# xen_daisy_motherboard.net
KiCad netlist of a schematic drawn in EAGLE
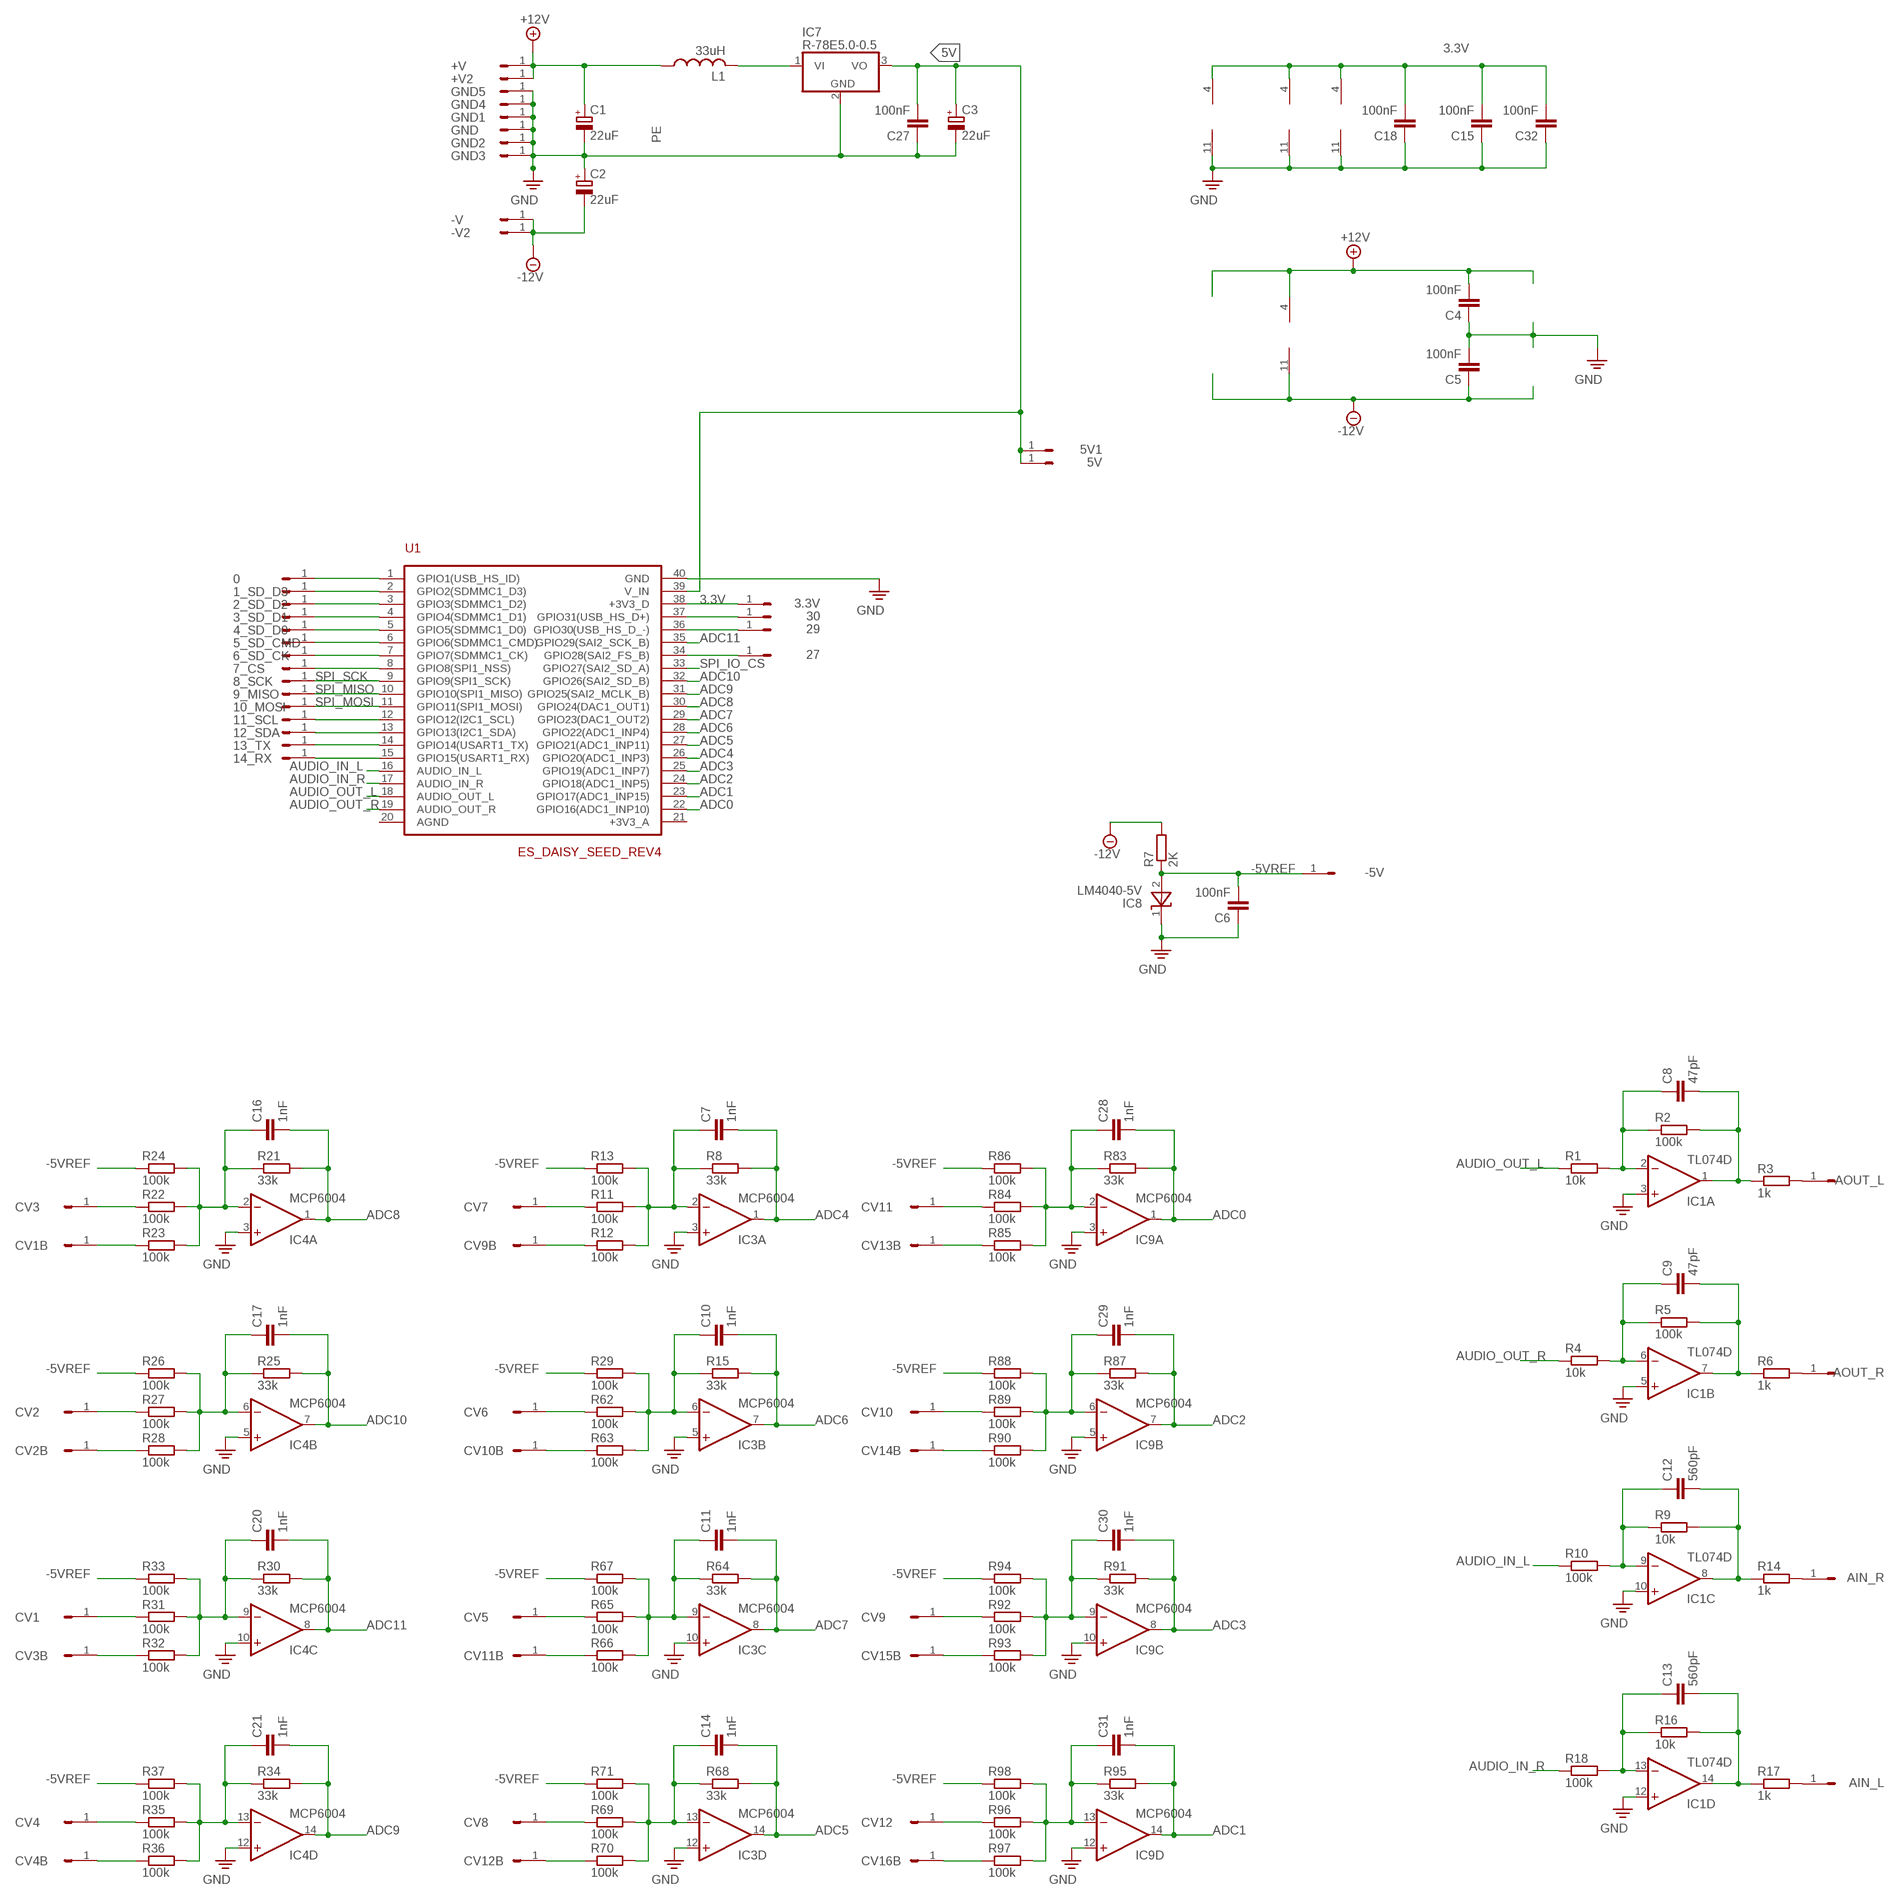
[diagram p0: schematic, sheet 1, part 1 of 2]
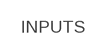
[diagram p1: schematic, sheet 1, part 2 of 2]

(export (version "E")
  (design (tool "Eeschema 10.0.6"))
  (components
    (comp (ref "+V")
      (value "HEADER/MALE/01")
      (footprint "eagle-import:HEADER_MALE_01")
      (fields (field (name "SPICEPREFIX") "X"))
      (libsource (lib "eagle-import") (part "HEADER/MALE/01"))
    )
    (comp (ref "+V2")
      (value "HEADER/MALE/01")
      (footprint "eagle-import:HEADER_MALE_01")
      (fields (field (name "SPICEPREFIX") "X"))
      (libsource (lib "eagle-import") (part "HEADER/MALE/01"))
    )
    (comp (ref "-5V")
      (value "HEADER/MALE/01")
      (footprint "eagle-import:HEADER_MALE_01")
      (fields (field (name "SPICEPREFIX") "X"))
      (libsource (lib "eagle-import") (part "HEADER/MALE/01"))
    )
    (comp (ref "-V")
      (value "HEADER/MALE/01")
      (footprint "eagle-import:HEADER_MALE_01")
      (fields (field (name "SPICEPREFIX") "X"))
      (libsource (lib "eagle-import") (part "HEADER/MALE/01"))
    )
    (comp (ref "-V2")
      (value "HEADER/MALE/01")
      (footprint "eagle-import:HEADER_MALE_01")
      (fields (field (name "SPICEPREFIX") "X"))
      (libsource (lib "eagle-import") (part "HEADER/MALE/01"))
    )
    (comp (ref "0")
      (value "HEADER/MALE/01")
      (footprint "eagle-import:HEADER_MALE_01")
      (fields (field (name "SPICEPREFIX") "X"))
      (libsource (lib "eagle-import") (part "HEADER/MALE/01"))
    )
    (comp (ref "1_SD_D3")
      (value "HEADER/MALE/01")
      (footprint "eagle-import:HEADER_MALE_01")
      (fields (field (name "SPICEPREFIX") "X"))
      (libsource (lib "eagle-import") (part "HEADER/MALE/01"))
    )
    (comp (ref "2_SD_D2")
      (value "HEADER/MALE/01")
      (footprint "eagle-import:HEADER_MALE_01")
      (fields (field (name "SPICEPREFIX") "X"))
      (libsource (lib "eagle-import") (part "HEADER/MALE/01"))
    )
    (comp (ref "3.3V")
      (value "HEADER/MALE/01")
      (footprint "eagle-import:HEADER_MALE_01")
      (fields (field (name "SPICEPREFIX") "X"))
      (libsource (lib "eagle-import") (part "HEADER/MALE/01"))
    )
    (comp (ref "3_SD_D1")
      (value "HEADER/MALE/01")
      (footprint "eagle-import:HEADER_MALE_01")
      (fields (field (name "SPICEPREFIX") "X"))
      (libsource (lib "eagle-import") (part "HEADER/MALE/01"))
    )
    (comp (ref "4_SD_D0")
      (value "HEADER/MALE/01")
      (footprint "eagle-import:HEADER_MALE_01")
      (fields (field (name "SPICEPREFIX") "X"))
      (libsource (lib "eagle-import") (part "HEADER/MALE/01"))
    )
    (comp (ref "5V")
      (value "HEADER/MALE/01")
      (footprint "eagle-import:HEADER_MALE_01")
      (fields (field (name "SPICEPREFIX") "X"))
      (libsource (lib "eagle-import") (part "HEADER/MALE/01"))
    )
    (comp (ref "5V1")
      (value "HEADER/MALE/01")
      (footprint "eagle-import:HEADER_MALE_01")
      (fields (field (name "SPICEPREFIX") "X"))
      (libsource (lib "eagle-import") (part "HEADER/MALE/01"))
    )
    (comp (ref "5_SD_CMD")
      (value "HEADER/MALE/01")
      (footprint "eagle-import:HEADER_MALE_01")
      (fields (field (name "SPICEPREFIX") "X"))
      (libsource (lib "eagle-import") (part "HEADER/MALE/01"))
    )
    (comp (ref "6_SD_CK")
      (value "HEADER/MALE/01")
      (footprint "eagle-import:HEADER_MALE_01")
      (fields (field (name "SPICEPREFIX") "X"))
      (libsource (lib "eagle-import") (part "HEADER/MALE/01"))
    )
    (comp (ref "7_CS")
      (value "HEADER/MALE/01")
      (footprint "eagle-import:HEADER_MALE_01")
      (fields (field (name "SPICEPREFIX") "X"))
      (libsource (lib "eagle-import") (part "HEADER/MALE/01"))
    )
    (comp (ref "8_SCK")
      (value "HEADER/MALE/01")
      (footprint "eagle-import:HEADER_MALE_01")
      (fields (field (name "SPICEPREFIX") "X"))
      (libsource (lib "eagle-import") (part "HEADER/MALE/01"))
    )
    (comp (ref "9_MISO")
      (value "HEADER/MALE/01")
      (footprint "eagle-import:HEADER_MALE_01")
      (fields (field (name "SPICEPREFIX") "X"))
      (libsource (lib "eagle-import") (part "HEADER/MALE/01"))
    )
    (comp (ref "10_MOSI")
      (value "HEADER/MALE/01")
      (footprint "eagle-import:HEADER_MALE_01")
      (fields (field (name "SPICEPREFIX") "X"))
      (libsource (lib "eagle-import") (part "HEADER/MALE/01"))
    )
    (comp (ref "11_SCL")
      (value "HEADER/MALE/01")
      (footprint "eagle-import:HEADER_MALE_01")
      (fields (field (name "SPICEPREFIX") "X"))
      (libsource (lib "eagle-import") (part "HEADER/MALE/01"))
    )
    (comp (ref "12_SDA")
      (value "HEADER/MALE/01")
      (footprint "eagle-import:HEADER_MALE_01")
      (fields (field (name "SPICEPREFIX") "X"))
      (libsource (lib "eagle-import") (part "HEADER/MALE/01"))
    )
    (comp (ref "13_TX")
      (value "HEADER/MALE/01")
      (footprint "eagle-import:HEADER_MALE_01")
      (fields (field (name "SPICEPREFIX") "X"))
      (libsource (lib "eagle-import") (part "HEADER/MALE/01"))
    )
    (comp (ref "14_RX")
      (value "HEADER/MALE/01")
      (footprint "eagle-import:HEADER_MALE_01")
      (fields (field (name "SPICEPREFIX") "X"))
      (libsource (lib "eagle-import") (part "HEADER/MALE/01"))
    )
    (comp (ref "27")
      (value "HEADER/MALE/01")
      (footprint "eagle-import:HEADER_MALE_01")
      (fields (field (name "SPICEPREFIX") "X"))
      (libsource (lib "eagle-import") (part "HEADER/MALE/01"))
    )
    (comp (ref "29")
      (value "HEADER/MALE/01")
      (footprint "eagle-import:HEADER_MALE_01")
      (fields (field (name "SPICEPREFIX") "X"))
      (libsource (lib "eagle-import") (part "HEADER/MALE/01"))
    )
    (comp (ref "30")
      (value "HEADER/MALE/01")
      (footprint "eagle-import:HEADER_MALE_01")
      (fields (field (name "SPICEPREFIX") "X"))
      (libsource (lib "eagle-import") (part "HEADER/MALE/01"))
    )
    (comp (ref "AIN_L")
      (value "HEADER/MALE/01")
      (footprint "eagle-import:HEADER_MALE_01")
      (fields (field (name "SPICEPREFIX") "X"))
      (libsource (lib "eagle-import") (part "HEADER/MALE/01"))
    )
    (comp (ref "AIN_R")
      (value "HEADER/MALE/01")
      (footprint "eagle-import:HEADER_MALE_01")
      (fields (field (name "SPICEPREFIX") "X"))
      (libsource (lib "eagle-import") (part "HEADER/MALE/01"))
    )
    (comp (ref "AOUT_L")
      (value "HEADER/MALE/01")
      (footprint "eagle-import:HEADER_MALE_01")
      (fields (field (name "SPICEPREFIX") "X"))
      (libsource (lib "eagle-import") (part "HEADER/MALE/01"))
    )
    (comp (ref "AOUT_R")
      (value "HEADER/MALE/01")
      (footprint "eagle-import:HEADER_MALE_01")
      (fields (field (name "SPICEPREFIX") "X"))
      (libsource (lib "eagle-import") (part "HEADER/MALE/01"))
    )
    (comp (ref "C1")
      (value "22uF")
      (footprint "eagle-import:PANASONIC_A")
      (fields (field (name "SPICEPREFIX") "C"))
      (libsource (lib "eagle-import") (part "CAPACITOR/POLARIZED"))
    )
    (comp (ref "C2")
      (value "22uF")
      (footprint "eagle-import:PANASONIC_A")
      (fields (field (name "SPICEPREFIX") "C"))
      (libsource (lib "eagle-import") (part "CAPACITOR/POLARIZED"))
    )
    (comp (ref "C3")
      (value "22uF")
      (footprint "eagle-import:PANASONIC_A")
      (fields (field (name "SPICEPREFIX") "C"))
      (libsource (lib "eagle-import") (part "CAPACITOR/POLARIZED"))
    )
    (comp (ref "C4")
      (value "100nF")
      (footprint "eagle-import:C0603")
      (libsource (lib "eagle-import") (part "CAPACITORC0603"))
    )
    (comp (ref "C5")
      (value "100nF")
      (footprint "eagle-import:C0603")
      (libsource (lib "eagle-import") (part "CAPACITORC0603"))
    )
    (comp (ref "C6")
      (value "100nF")
      (footprint "eagle-import:C0603")
      (libsource (lib "eagle-import") (part "CAPACITORC0603"))
    )
    (comp (ref "C7")
      (value "1nF")
      (footprint "eagle-import:C0603")
      (libsource (lib "eagle-import") (part "CAPACITORC0603"))
    )
    (comp (ref "C8")
      (value "47pF")
      (footprint "eagle-import:C0603")
      (libsource (lib "eagle-import") (part "CAPACITORC0603"))
    )
    (comp (ref "C9")
      (value "47pF")
      (footprint "eagle-import:C0603")
      (libsource (lib "eagle-import") (part "CAPACITORC0603"))
    )
    (comp (ref "C10")
      (value "1nF")
      (footprint "eagle-import:C0603")
      (libsource (lib "eagle-import") (part "CAPACITORC0603"))
    )
    (comp (ref "C11")
      (value "1nF")
      (footprint "eagle-import:C0603")
      (libsource (lib "eagle-import") (part "CAPACITORC0603"))
    )
    (comp (ref "C12")
      (value "560pF")
      (footprint "eagle-import:C0603")
      (libsource (lib "eagle-import") (part "CAPACITORC0603"))
    )
    (comp (ref "C13")
      (value "560pF")
      (footprint "eagle-import:C0603")
      (libsource (lib "eagle-import") (part "CAPACITORC0603"))
    )
    (comp (ref "C14")
      (value "1nF")
      (footprint "eagle-import:C0603")
      (libsource (lib "eagle-import") (part "CAPACITORC0603"))
    )
    (comp (ref "C15")
      (value "100nF")
      (footprint "eagle-import:C0603")
      (libsource (lib "eagle-import") (part "CAPACITORC0603"))
    )
    (comp (ref "C16")
      (value "1nF")
      (footprint "eagle-import:C0603")
      (libsource (lib "eagle-import") (part "CAPACITORC0603"))
    )
    (comp (ref "C17")
      (value "1nF")
      (footprint "eagle-import:C0603")
      (libsource (lib "eagle-import") (part "CAPACITORC0603"))
    )
    (comp (ref "C18")
      (value "100nF")
      (footprint "eagle-import:C0603")
      (libsource (lib "eagle-import") (part "CAPACITORC0603"))
    )
    (comp (ref "C20")
      (value "1nF")
      (footprint "eagle-import:C0603")
      (libsource (lib "eagle-import") (part "CAPACITORC0603"))
    )
    (comp (ref "C21")
      (value "1nF")
      (footprint "eagle-import:C0603")
      (libsource (lib "eagle-import") (part "CAPACITORC0603"))
    )
    (comp (ref "C27")
      (value "100nF")
      (footprint "eagle-import:C0603")
      (libsource (lib "eagle-import") (part "CAPACITORC0603"))
    )
    (comp (ref "C28")
      (value "1nF")
      (footprint "eagle-import:C0603")
      (libsource (lib "eagle-import") (part "CAPACITORC0603"))
    )
    (comp (ref "C29")
      (value "1nF")
      (footprint "eagle-import:C0603")
      (libsource (lib "eagle-import") (part "CAPACITORC0603"))
    )
    (comp (ref "C30")
      (value "1nF")
      (footprint "eagle-import:C0603")
      (libsource (lib "eagle-import") (part "CAPACITORC0603"))
    )
    (comp (ref "C31")
      (value "1nF")
      (footprint "eagle-import:C0603")
      (libsource (lib "eagle-import") (part "CAPACITORC0603"))
    )
    (comp (ref "C32")
      (value "100nF")
      (footprint "eagle-import:C0603")
      (libsource (lib "eagle-import") (part "CAPACITORC0603"))
    )
    (comp (ref "CV1")
      (value "HEADER/MALE/01")
      (footprint "eagle-import:HEADER_MALE_01")
      (fields (field (name "SPICEPREFIX") "X"))
      (libsource (lib "eagle-import") (part "HEADER/MALE/01"))
    )
    (comp (ref "CV1B")
      (value "HEADER/MALE/01")
      (footprint "eagle-import:HEADER_MALE_01")
      (fields (field (name "SPICEPREFIX") "X"))
      (libsource (lib "eagle-import") (part "HEADER/MALE/01"))
    )
    (comp (ref "CV2")
      (value "HEADER/MALE/01")
      (footprint "eagle-import:HEADER_MALE_01")
      (fields (field (name "SPICEPREFIX") "X"))
      (libsource (lib "eagle-import") (part "HEADER/MALE/01"))
    )
    (comp (ref "CV2B")
      (value "HEADER/MALE/01")
      (footprint "eagle-import:HEADER_MALE_01")
      (fields (field (name "SPICEPREFIX") "X"))
      (libsource (lib "eagle-import") (part "HEADER/MALE/01"))
    )
    (comp (ref "CV3")
      (value "HEADER/MALE/01")
      (footprint "eagle-import:HEADER_MALE_01")
      (fields (field (name "SPICEPREFIX") "X"))
      (libsource (lib "eagle-import") (part "HEADER/MALE/01"))
    )
    (comp (ref "CV3B")
      (value "HEADER/MALE/01")
      (footprint "eagle-import:HEADER_MALE_01")
      (fields (field (name "SPICEPREFIX") "X"))
      (libsource (lib "eagle-import") (part "HEADER/MALE/01"))
    )
    (comp (ref "CV4")
      (value "HEADER/MALE/01")
      (footprint "eagle-import:HEADER_MALE_01")
      (fields (field (name "SPICEPREFIX") "X"))
      (libsource (lib "eagle-import") (part "HEADER/MALE/01"))
    )
    (comp (ref "CV4B")
      (value "HEADER/MALE/01")
      (footprint "eagle-import:HEADER_MALE_01")
      (fields (field (name "SPICEPREFIX") "X"))
      (libsource (lib "eagle-import") (part "HEADER/MALE/01"))
    )
    (comp (ref "CV5")
      (value "HEADER/MALE/01")
      (footprint "eagle-import:HEADER_MALE_01")
      (fields (field (name "SPICEPREFIX") "X"))
      (libsource (lib "eagle-import") (part "HEADER/MALE/01"))
    )
    (comp (ref "CV6")
      (value "HEADER/MALE/01")
      (footprint "eagle-import:HEADER_MALE_01")
      (fields (field (name "SPICEPREFIX") "X"))
      (libsource (lib "eagle-import") (part "HEADER/MALE/01"))
    )
    (comp (ref "CV7")
      (value "HEADER/MALE/01")
      (footprint "eagle-import:HEADER_MALE_01")
      (fields (field (name "SPICEPREFIX") "X"))
      (libsource (lib "eagle-import") (part "HEADER/MALE/01"))
    )
    (comp (ref "CV8")
      (value "HEADER/MALE/01")
      (footprint "eagle-import:HEADER_MALE_01")
      (fields (field (name "SPICEPREFIX") "X"))
      (libsource (lib "eagle-import") (part "HEADER/MALE/01"))
    )
    (comp (ref "CV9")
      (value "HEADER/MALE/01")
      (footprint "eagle-import:HEADER_MALE_01")
      (fields (field (name "SPICEPREFIX") "X"))
      (libsource (lib "eagle-import") (part "HEADER/MALE/01"))
    )
    (comp (ref "CV9B")
      (value "HEADER/MALE/01")
      (footprint "eagle-import:HEADER_MALE_01")
      (fields (field (name "SPICEPREFIX") "X"))
      (libsource (lib "eagle-import") (part "HEADER/MALE/01"))
    )
    (comp (ref "CV10")
      (value "HEADER/MALE/01")
      (footprint "eagle-import:HEADER_MALE_01")
      (fields (field (name "SPICEPREFIX") "X"))
      (libsource (lib "eagle-import") (part "HEADER/MALE/01"))
    )
    (comp (ref "CV10B")
      (value "HEADER/MALE/01")
      (footprint "eagle-import:HEADER_MALE_01")
      (fields (field (name "SPICEPREFIX") "X"))
      (libsource (lib "eagle-import") (part "HEADER/MALE/01"))
    )
    (comp (ref "CV11")
      (value "HEADER/MALE/01")
      (footprint "eagle-import:HEADER_MALE_01")
      (fields (field (name "SPICEPREFIX") "X"))
      (libsource (lib "eagle-import") (part "HEADER/MALE/01"))
    )
    (comp (ref "CV11B")
      (value "HEADER/MALE/01")
      (footprint "eagle-import:HEADER_MALE_01")
      (fields (field (name "SPICEPREFIX") "X"))
      (libsource (lib "eagle-import") (part "HEADER/MALE/01"))
    )
    (comp (ref "CV12")
      (value "HEADER/MALE/01")
      (footprint "eagle-import:HEADER_MALE_01")
      (fields (field (name "SPICEPREFIX") "X"))
      (libsource (lib "eagle-import") (part "HEADER/MALE/01"))
    )
    (comp (ref "CV12B")
      (value "HEADER/MALE/01")
      (footprint "eagle-import:HEADER_MALE_01")
      (fields (field (name "SPICEPREFIX") "X"))
      (libsource (lib "eagle-import") (part "HEADER/MALE/01"))
    )
    (comp (ref "CV13B")
      (value "HEADER/MALE/01")
      (footprint "eagle-import:HEADER_MALE_01")
      (fields (field (name "SPICEPREFIX") "X"))
      (libsource (lib "eagle-import") (part "HEADER/MALE/01"))
    )
    (comp (ref "CV14B")
      (value "HEADER/MALE/01")
      (footprint "eagle-import:HEADER_MALE_01")
      (fields (field (name "SPICEPREFIX") "X"))
      (libsource (lib "eagle-import") (part "HEADER/MALE/01"))
    )
    (comp (ref "CV15B")
      (value "HEADER/MALE/01")
      (footprint "eagle-import:HEADER_MALE_01")
      (fields (field (name "SPICEPREFIX") "X"))
      (libsource (lib "eagle-import") (part "HEADER/MALE/01"))
    )
    (comp (ref "CV16B")
      (value "HEADER/MALE/01")
      (footprint "eagle-import:HEADER_MALE_01")
      (fields (field (name "SPICEPREFIX") "X"))
      (libsource (lib "eagle-import") (part "HEADER/MALE/01"))
    )
    (comp (ref "GND")
      (value "HEADER/MALE/01")
      (footprint "eagle-import:HEADER_MALE_01")
      (fields (field (name "SPICEPREFIX") "X"))
      (libsource (lib "eagle-import") (part "HEADER/MALE/01"))
    )
    (comp (ref "GND1")
      (value "HEADER/MALE/01")
      (footprint "eagle-import:HEADER_MALE_01")
      (fields (field (name "SPICEPREFIX") "X"))
      (libsource (lib "eagle-import") (part "HEADER/MALE/01"))
    )
    (comp (ref "GND2")
      (value "HEADER/MALE/01")
      (footprint "eagle-import:HEADER_MALE_01")
      (fields (field (name "SPICEPREFIX") "X"))
      (libsource (lib "eagle-import") (part "HEADER/MALE/01"))
    )
    (comp (ref "GND3")
      (value "HEADER/MALE/01")
      (footprint "eagle-import:HEADER_MALE_01")
      (fields (field (name "SPICEPREFIX") "X"))
      (libsource (lib "eagle-import") (part "HEADER/MALE/01"))
    )
    (comp (ref "GND4")
      (value "HEADER/MALE/01")
      (footprint "eagle-import:HEADER_MALE_01")
      (fields (field (name "SPICEPREFIX") "X"))
      (libsource (lib "eagle-import") (part "HEADER/MALE/01"))
    )
    (comp (ref "GND5")
      (value "HEADER/MALE/01")
      (footprint "eagle-import:HEADER_MALE_01")
      (fields (field (name "SPICEPREFIX") "X"))
      (libsource (lib "eagle-import") (part "HEADER/MALE/01"))
    )
    (comp (ref "IC1")
      (value "TL074D")
      (footprint "eagle-import:SO14")
      (libsource (lib "eagle-import") (part "TL074D"))
    )
    (comp (ref "IC3")
      (value "MCP6004")
      (footprint "eagle-import:SO14")
      (libsource (lib "eagle-import") (part "TL074D"))
    )
    (comp (ref "IC4")
      (value "MCP6004")
      (footprint "eagle-import:SO14")
      (libsource (lib "eagle-import") (part "TL074D"))
    )
    (comp (ref "IC7")
      (value "R-78E5.0-0.5")
      (footprint "eagle-import:WE78")
      (libsource (lib "eagle-import") (part "WE173950378"))
    )
    (comp (ref "IC8")
      (value "LM4040-5V")
      (footprint "eagle-import:SOT-23")
      (libsource (lib "eagle-import") (part "LM4040CYM3-2.5"))
    )
    (comp (ref "IC9")
      (value "MCP6004")
      (footprint "eagle-import:SO14")
      (libsource (lib "eagle-import") (part "TL074D"))
    )
    (comp (ref "L1")
      (value "33uH")
      (footprint "eagle-import:L2012C")
      (libsource (lib "eagle-import") (part "INDUCTORL2012C"))
    )
    (comp (ref "R1")
      (value "10k")
      (footprint "eagle-import:R0603")
      (libsource (lib "eagle-import") (part "RESISTOR"))
    )
    (comp (ref "R2")
      (value "100k")
      (footprint "eagle-import:R0603")
      (libsource (lib "eagle-import") (part "RESISTOR"))
    )
    (comp (ref "R3")
      (value "1k")
      (footprint "eagle-import:R0603")
      (libsource (lib "eagle-import") (part "RESISTOR"))
    )
    (comp (ref "R4")
      (value "10k")
      (footprint "eagle-import:R0603")
      (libsource (lib "eagle-import") (part "RESISTOR"))
    )
    (comp (ref "R5")
      (value "100k")
      (footprint "eagle-import:R0603")
      (libsource (lib "eagle-import") (part "RESISTOR"))
    )
    (comp (ref "R6")
      (value "1k")
      (footprint "eagle-import:R0603")
      (libsource (lib "eagle-import") (part "RESISTOR"))
    )
    (comp (ref "R7")
      (value "2K")
      (footprint "eagle-import:R0603")
      (libsource (lib "eagle-import") (part "RESISTOR"))
    )
    (comp (ref "R8")
      (value "33k")
      (footprint "eagle-import:R0603")
      (libsource (lib "eagle-import") (part "RESISTOR"))
    )
    (comp (ref "R9")
      (value "10k")
      (footprint "eagle-import:R0603")
      (libsource (lib "eagle-import") (part "RESISTOR"))
    )
    (comp (ref "R10")
      (value "100k")
      (footprint "eagle-import:R0603")
      (libsource (lib "eagle-import") (part "RESISTOR"))
    )
    (comp (ref "R11")
      (value "100k")
      (footprint "eagle-import:R0603")
      (libsource (lib "eagle-import") (part "RESISTOR"))
    )
    (comp (ref "R12")
      (value "100k")
      (footprint "eagle-import:R0603")
      (libsource (lib "eagle-import") (part "RESISTOR"))
    )
    (comp (ref "R13")
      (value "100k")
      (footprint "eagle-import:R0603")
      (libsource (lib "eagle-import") (part "RESISTOR"))
    )
    (comp (ref "R14")
      (value "1k")
      (footprint "eagle-import:R0603")
      (libsource (lib "eagle-import") (part "RESISTOR"))
    )
    (comp (ref "R15")
      (value "33k")
      (footprint "eagle-import:R0603")
      (libsource (lib "eagle-import") (part "RESISTOR"))
    )
    (comp (ref "R16")
      (value "10k")
      (footprint "eagle-import:R0603")
      (libsource (lib "eagle-import") (part "RESISTOR"))
    )
    (comp (ref "R17")
      (value "1k")
      (footprint "eagle-import:R0603")
      (libsource (lib "eagle-import") (part "RESISTOR"))
    )
    (comp (ref "R18")
      (value "100k")
      (footprint "eagle-import:R0603")
      (libsource (lib "eagle-import") (part "RESISTOR"))
    )
    (comp (ref "R21")
      (value "33k")
      (footprint "eagle-import:R0603")
      (libsource (lib "eagle-import") (part "RESISTOR"))
    )
    (comp (ref "R22")
      (value "100k")
      (footprint "eagle-import:R0603")
      (libsource (lib "eagle-import") (part "RESISTOR"))
    )
    (comp (ref "R23")
      (value "100k")
      (footprint "eagle-import:R0603")
      (libsource (lib "eagle-import") (part "RESISTOR"))
    )
    (comp (ref "R24")
      (value "100k")
      (footprint "eagle-import:R0603")
      (libsource (lib "eagle-import") (part "RESISTOR"))
    )
    (comp (ref "R25")
      (value "33k")
      (footprint "eagle-import:R0603")
      (libsource (lib "eagle-import") (part "RESISTOR"))
    )
    (comp (ref "R26")
      (value "100k")
      (footprint "eagle-import:R0603")
      (libsource (lib "eagle-import") (part "RESISTOR"))
    )
    (comp (ref "R27")
      (value "100k")
      (footprint "eagle-import:R0603")
      (libsource (lib "eagle-import") (part "RESISTOR"))
    )
    (comp (ref "R28")
      (value "100k")
      (footprint "eagle-import:R0603")
      (libsource (lib "eagle-import") (part "RESISTOR"))
    )
    (comp (ref "R29")
      (value "100k")
      (footprint "eagle-import:R0603")
      (libsource (lib "eagle-import") (part "RESISTOR"))
    )
    (comp (ref "R30")
      (value "33k")
      (footprint "eagle-import:R0603")
      (libsource (lib "eagle-import") (part "RESISTOR"))
    )
    (comp (ref "R31")
      (value "100k")
      (footprint "eagle-import:R0603")
      (libsource (lib "eagle-import") (part "RESISTOR"))
    )
    (comp (ref "R32")
      (value "100k")
      (footprint "eagle-import:R0603")
      (libsource (lib "eagle-import") (part "RESISTOR"))
    )
    (comp (ref "R33")
      (value "100k")
      (footprint "eagle-import:R0603")
      (libsource (lib "eagle-import") (part "RESISTOR"))
    )
    (comp (ref "R34")
      (value "33k")
      (footprint "eagle-import:R0603")
      (libsource (lib "eagle-import") (part "RESISTOR"))
    )
    (comp (ref "R35")
      (value "100k")
      (footprint "eagle-import:R0603")
      (libsource (lib "eagle-import") (part "RESISTOR"))
    )
    (comp (ref "R36")
      (value "100k")
      (footprint "eagle-import:R0603")
      (libsource (lib "eagle-import") (part "RESISTOR"))
    )
    (comp (ref "R37")
      (value "100k")
      (footprint "eagle-import:R0603")
      (libsource (lib "eagle-import") (part "RESISTOR"))
    )
    (comp (ref "R62")
      (value "100k")
      (footprint "eagle-import:R0603")
      (libsource (lib "eagle-import") (part "RESISTOR"))
    )
    (comp (ref "R63")
      (value "100k")
      (footprint "eagle-import:R0603")
      (libsource (lib "eagle-import") (part "RESISTOR"))
    )
    (comp (ref "R64")
      (value "33k")
      (footprint "eagle-import:R0603")
      (libsource (lib "eagle-import") (part "RESISTOR"))
    )
    (comp (ref "R65")
      (value "100k")
      (footprint "eagle-import:R0603")
      (libsource (lib "eagle-import") (part "RESISTOR"))
    )
    (comp (ref "R66")
      (value "100k")
      (footprint "eagle-import:R0603")
      (libsource (lib "eagle-import") (part "RESISTOR"))
    )
    (comp (ref "R67")
      (value "100k")
      (footprint "eagle-import:R0603")
      (libsource (lib "eagle-import") (part "RESISTOR"))
    )
    (comp (ref "R68")
      (value "33k")
      (footprint "eagle-import:R0603")
      (libsource (lib "eagle-import") (part "RESISTOR"))
    )
    (comp (ref "R69")
      (value "100k")
      (footprint "eagle-import:R0603")
      (libsource (lib "eagle-import") (part "RESISTOR"))
    )
    (comp (ref "R70")
      (value "100k")
      (footprint "eagle-import:R0603")
      (libsource (lib "eagle-import") (part "RESISTOR"))
    )
    (comp (ref "R71")
      (value "100k")
      (footprint "eagle-import:R0603")
      (libsource (lib "eagle-import") (part "RESISTOR"))
    )
    (comp (ref "R83")
      (value "33k")
      (footprint "eagle-import:R0603")
      (libsource (lib "eagle-import") (part "RESISTOR"))
    )
    (comp (ref "R84")
      (value "100k")
      (footprint "eagle-import:R0603")
      (libsource (lib "eagle-import") (part "RESISTOR"))
    )
    (comp (ref "R85")
      (value "100k")
      (footprint "eagle-import:R0603")
      (libsource (lib "eagle-import") (part "RESISTOR"))
    )
    (comp (ref "R86")
      (value "100k")
      (footprint "eagle-import:R0603")
      (libsource (lib "eagle-import") (part "RESISTOR"))
    )
    (comp (ref "R87")
      (value "33k")
      (footprint "eagle-import:R0603")
      (libsource (lib "eagle-import") (part "RESISTOR"))
    )
    (comp (ref "R88")
      (value "100k")
      (footprint "eagle-import:R0603")
      (libsource (lib "eagle-import") (part "RESISTOR"))
    )
    (comp (ref "R89")
      (value "100k")
      (footprint "eagle-import:R0603")
      (libsource (lib "eagle-import") (part "RESISTOR"))
    )
    (comp (ref "R90")
      (value "100k")
      (footprint "eagle-import:R0603")
      (libsource (lib "eagle-import") (part "RESISTOR"))
    )
    (comp (ref "R91")
      (value "33k")
      (footprint "eagle-import:R0603")
      (libsource (lib "eagle-import") (part "RESISTOR"))
    )
    (comp (ref "R92")
      (value "100k")
      (footprint "eagle-import:R0603")
      (libsource (lib "eagle-import") (part "RESISTOR"))
    )
    (comp (ref "R93")
      (value "100k")
      (footprint "eagle-import:R0603")
      (libsource (lib "eagle-import") (part "RESISTOR"))
    )
    (comp (ref "R94")
      (value "100k")
      (footprint "eagle-import:R0603")
      (libsource (lib "eagle-import") (part "RESISTOR"))
    )
    (comp (ref "R95")
      (value "33k")
      (footprint "eagle-import:R0603")
      (libsource (lib "eagle-import") (part "RESISTOR"))
    )
    (comp (ref "R96")
      (value "100k")
      (footprint "eagle-import:R0603")
      (libsource (lib "eagle-import") (part "RESISTOR"))
    )
    (comp (ref "R97")
      (value "100k")
      (footprint "eagle-import:R0603")
      (libsource (lib "eagle-import") (part "RESISTOR"))
    )
    (comp (ref "R98")
      (value "100k")
      (footprint "eagle-import:R0603")
      (libsource (lib "eagle-import") (part "RESISTOR"))
    )
    (comp (ref "U1")
      (value "ES_DAISY_SEED_REV4")
      (footprint "eagle-import:ES_DAISY_SEED")
      (libsource (lib "eagle-import") (part "ES_DAISY_SEED_REV4"))
    )
  )
  (nets
    (net (code "1") (name "+12V") (class "Default")
      (node (ref "+V") (pin "1") (pinfunction "3_1") (pintype "passive"))
      (node (ref "+V2") (pin "1") (pinfunction "3_1") (pintype "passive"))
      (node (ref "C1") (pin "+") (pinfunction "+_+") (pintype "passive"))
      (node (ref "C4") (pin "2") (pinfunction "2_2") (pintype "passive"))
      (node (ref "IC1") (pin "4") (pinfunction "V+_4") (pintype "power_in"))
      (node (ref "L1") (pin "1") (pinfunction "1_1") (pintype "passive"))
    )
    (net (code "2") (name "-12V") (class "Default")
      (node (ref "-V") (pin "1") (pinfunction "3_1") (pintype "passive"))
      (node (ref "-V2") (pin "1") (pinfunction "3_1") (pintype "passive"))
      (node (ref "C2") (pin "-") (pinfunction "-_-") (pintype "passive"))
      (node (ref "C5") (pin "1") (pinfunction "1_1") (pintype "passive"))
      (node (ref "IC1") (pin "11") (pinfunction "V-_11") (pintype "power_in"))
      (node (ref "R7") (pin "2") (pinfunction "2_2") (pintype "passive"))
    )
    (net (code "3") (name "/-5VREF") (class "Default")
      (node (ref "-5V") (pin "1") (pinfunction "3_1") (pintype "passive"))
      (node (ref "C6") (pin "2") (pinfunction "2_2") (pintype "passive"))
      (node (ref "IC8") (pin "2") (pinfunction "A_2") (pintype "output"))
      (node (ref "R13") (pin "1") (pinfunction "1_1") (pintype "passive"))
      (node (ref "R24") (pin "1") (pinfunction "1_1") (pintype "passive"))
      (node (ref "R26") (pin "1") (pinfunction "1_1") (pintype "passive"))
      (node (ref "R29") (pin "1") (pinfunction "1_1") (pintype "passive"))
      (node (ref "R33") (pin "1") (pinfunction "1_1") (pintype "passive"))
      (node (ref "R37") (pin "1") (pinfunction "1_1") (pintype "passive"))
      (node (ref "R67") (pin "1") (pinfunction "1_1") (pintype "passive"))
      (node (ref "R7") (pin "1") (pinfunction "1_1") (pintype "passive"))
      (node (ref "R71") (pin "1") (pinfunction "1_1") (pintype "passive"))
      (node (ref "R86") (pin "1") (pinfunction "1_1") (pintype "passive"))
      (node (ref "R88") (pin "1") (pinfunction "1_1") (pintype "passive"))
      (node (ref "R94") (pin "1") (pinfunction "1_1") (pintype "passive"))
      (node (ref "R98") (pin "1") (pinfunction "1_1") (pintype "passive"))
    )
    (net (code "4") (name "/3.3V") (class "Default")
      (node (ref "3.3V") (pin "1") (pinfunction "3_1") (pintype "passive"))
      (node (ref "C15") (pin "2") (pinfunction "2_2") (pintype "passive"))
      (node (ref "C18") (pin "2") (pinfunction "2_2") (pintype "passive"))
      (node (ref "C32") (pin "2") (pinfunction "2_2") (pintype "passive"))
      (node (ref "IC3") (pin "4") (pinfunction "V+_4") (pintype "power_in"))
      (node (ref "IC4") (pin "4") (pinfunction "V+_4") (pintype "power_in"))
      (node (ref "IC9") (pin "4") (pinfunction "V+_4") (pintype "power_in"))
      (node (ref "U1") (pin "38") (pinfunction "+3V3_D_38") (pintype "bidirectional"))
    )
    (net (code "5") (name "/ADC0") (class "Default")
      (node (ref "C28") (pin "2") (pinfunction "2_2") (pintype "passive"))
      (node (ref "IC9") (pin "1") (pinfunction "OUT_1") (pintype "output"))
      (node (ref "R83") (pin "2") (pinfunction "2_2") (pintype "passive"))
      (node (ref "U1") (pin "22") (pinfunction "GPIO16(ADC1_INP10)_22") (pintype "bidirectional"))
    )
    (net (code "6") (name "/ADC1") (class "Default")
      (node (ref "C31") (pin "2") (pinfunction "2_2") (pintype "passive"))
      (node (ref "IC9") (pin "14") (pinfunction "OUT_14") (pintype "output"))
      (node (ref "R95") (pin "2") (pinfunction "2_2") (pintype "passive"))
      (node (ref "U1") (pin "23") (pinfunction "GPIO17(ADC1_INP15)_23") (pintype "bidirectional"))
    )
    (net (code "7") (name "/ADC2") (class "Default")
      (node (ref "C29") (pin "2") (pinfunction "2_2") (pintype "passive"))
      (node (ref "IC9") (pin "7") (pinfunction "OUT_7") (pintype "output"))
      (node (ref "R87") (pin "2") (pinfunction "2_2") (pintype "passive"))
      (node (ref "U1") (pin "24") (pinfunction "GPIO18(ADC1_INP5)_24") (pintype "bidirectional"))
    )
    (net (code "8") (name "/ADC3") (class "Default")
      (node (ref "C30") (pin "2") (pinfunction "2_2") (pintype "passive"))
      (node (ref "IC9") (pin "8") (pinfunction "OUT_8") (pintype "output"))
      (node (ref "R91") (pin "2") (pinfunction "2_2") (pintype "passive"))
      (node (ref "U1") (pin "25") (pinfunction "GPIO19(ADC1_INP7)_25") (pintype "bidirectional"))
    )
    (net (code "9") (name "/ADC4") (class "Default")
      (node (ref "C7") (pin "2") (pinfunction "2_2") (pintype "passive"))
      (node (ref "IC3") (pin "1") (pinfunction "OUT_1") (pintype "output"))
      (node (ref "R8") (pin "2") (pinfunction "2_2") (pintype "passive"))
      (node (ref "U1") (pin "26") (pinfunction "GPIO20(ADC1_INP3)_26") (pintype "bidirectional"))
    )
    (net (code "10") (name "/ADC5") (class "Default")
      (node (ref "C14") (pin "2") (pinfunction "2_2") (pintype "passive"))
      (node (ref "IC3") (pin "14") (pinfunction "OUT_14") (pintype "output"))
      (node (ref "R68") (pin "2") (pinfunction "2_2") (pintype "passive"))
      (node (ref "U1") (pin "27") (pinfunction "GPIO21(ADC1_INP11)_27") (pintype "bidirectional"))
    )
    (net (code "11") (name "/ADC6") (class "Default")
      (node (ref "C10") (pin "2") (pinfunction "2_2") (pintype "passive"))
      (node (ref "IC3") (pin "7") (pinfunction "OUT_7") (pintype "output"))
      (node (ref "R15") (pin "2") (pinfunction "2_2") (pintype "passive"))
      (node (ref "U1") (pin "28") (pinfunction "GPIO22(ADC1_INP4)_28") (pintype "bidirectional"))
    )
    (net (code "12") (name "/ADC7") (class "Default")
      (node (ref "C11") (pin "2") (pinfunction "2_2") (pintype "passive"))
      (node (ref "IC3") (pin "8") (pinfunction "OUT_8") (pintype "output"))
      (node (ref "R64") (pin "2") (pinfunction "2_2") (pintype "passive"))
      (node (ref "U1") (pin "29") (pinfunction "GPIO23(DAC1_OUT2)_29") (pintype "bidirectional"))
    )
    (net (code "13") (name "/ADC8") (class "Default")
      (node (ref "C16") (pin "2") (pinfunction "2_2") (pintype "passive"))
      (node (ref "IC4") (pin "1") (pinfunction "OUT_1") (pintype "output"))
      (node (ref "R21") (pin "2") (pinfunction "2_2") (pintype "passive"))
      (node (ref "U1") (pin "30") (pinfunction "GPIO24(DAC1_OUT1)_30") (pintype "bidirectional"))
    )
    (net (code "14") (name "/ADC9") (class "Default")
      (node (ref "C21") (pin "2") (pinfunction "2_2") (pintype "passive"))
      (node (ref "IC4") (pin "14") (pinfunction "OUT_14") (pintype "output"))
      (node (ref "R34") (pin "2") (pinfunction "2_2") (pintype "passive"))
      (node (ref "U1") (pin "31") (pinfunction "GPIO25(SAI2_MCLK_B)_31") (pintype "bidirectional"))
    )
    (net (code "15") (name "/ADC10") (class "Default")
      (node (ref "C17") (pin "2") (pinfunction "2_2") (pintype "passive"))
      (node (ref "IC4") (pin "7") (pinfunction "OUT_7") (pintype "output"))
      (node (ref "R25") (pin "2") (pinfunction "2_2") (pintype "passive"))
      (node (ref "U1") (pin "32") (pinfunction "GPIO26(SAI2_SD_B)_32") (pintype "bidirectional"))
    )
    (net (code "16") (name "/ADC11") (class "Default")
      (node (ref "C20") (pin "2") (pinfunction "2_2") (pintype "passive"))
      (node (ref "IC4") (pin "8") (pinfunction "OUT_8") (pintype "output"))
      (node (ref "R30") (pin "2") (pinfunction "2_2") (pintype "passive"))
      (node (ref "U1") (pin "35") (pinfunction "GPIO29(SAI2_SCK_B)_35") (pintype "bidirectional"))
    )
    (net (code "17") (name "/AUDIO_IN_L") (class "Default")
      (node (ref "R10") (pin "1") (pinfunction "1_1") (pintype "passive"))
      (node (ref "U1") (pin "16") (pinfunction "AUDIO_IN_L_16") (pintype "bidirectional"))
    )
    (net (code "18") (name "/AUDIO_IN_R") (class "Default")
      (node (ref "R18") (pin "1") (pinfunction "1_1") (pintype "passive"))
      (node (ref "U1") (pin "17") (pinfunction "AUDIO_IN_R_17") (pintype "bidirectional"))
    )
    (net (code "19") (name "/AUDIO_OUT_L") (class "Default")
      (node (ref "R1") (pin "1") (pinfunction "1_1") (pintype "passive"))
      (node (ref "U1") (pin "18") (pinfunction "AUDIO_OUT_L_18") (pintype "bidirectional"))
    )
    (net (code "20") (name "/AUDIO_OUT_R") (class "Default")
      (node (ref "R4") (pin "1") (pinfunction "1_1") (pintype "passive"))
      (node (ref "U1") (pin "19") (pinfunction "AUDIO_OUT_R_19") (pintype "bidirectional"))
    )
    (net (code "21") (name "/SPI_IO_CS") (class "Default")
      (node (ref "U1") (pin "33") (pinfunction "GPIO27(SAI2_SD_A)_33") (pintype "bidirectional"))
    )
    (net (code "22") (name "/SPI_MISO") (class "Default")
      (node (ref "9_MISO") (pin "1") (pinfunction "3_1") (pintype "passive"))
      (node (ref "U1") (pin "10") (pinfunction "GPIO10(SPI1_MISO)_10") (pintype "bidirectional"))
    )
    (net (code "23") (name "/SPI_MOSI") (class "Default")
      (node (ref "10_MOSI") (pin "1") (pinfunction "3_1") (pintype "passive"))
      (node (ref "U1") (pin "11") (pinfunction "GPIO11(SPI1_MOSI)_11") (pintype "bidirectional"))
    )
    (net (code "24") (name "/SPI_SCK") (class "Default")
      (node (ref "8_SCK") (pin "1") (pinfunction "3_1") (pintype "passive"))
      (node (ref "U1") (pin "9") (pinfunction "GPIO9(SPI1_SCK)_9") (pintype "bidirectional"))
    )
    (net (code "25") (name "5V") (class "Default")
      (node (ref "5V") (pin "1") (pinfunction "3_1") (pintype "passive"))
      (node (ref "5V1") (pin "1") (pinfunction "3_1") (pintype "passive"))
      (node (ref "C27") (pin "2") (pinfunction "2_2") (pintype "passive"))
      (node (ref "C3") (pin "+") (pinfunction "+_+") (pintype "passive"))
      (node (ref "IC7") (pin "3") (pinfunction "VO_3") (pintype "passive"))
      (node (ref "U1") (pin "39") (pinfunction "V_IN_39") (pintype "bidirectional"))
    )
    (net (code "26") (name "GND") (class "Default")
      (node (ref "C1") (pin "-") (pinfunction "-_-") (pintype "passive"))
      (node (ref "C15") (pin "1") (pinfunction "1_1") (pintype "passive"))
      (node (ref "C18") (pin "1") (pinfunction "1_1") (pintype "passive"))
      (node (ref "C2") (pin "+") (pinfunction "+_+") (pintype "passive"))
      (node (ref "C27") (pin "1") (pinfunction "1_1") (pintype "passive"))
      (node (ref "C3") (pin "-") (pinfunction "-_-") (pintype "passive"))
      (node (ref "C32") (pin "1") (pinfunction "1_1") (pintype "passive"))
      (node (ref "C4") (pin "1") (pinfunction "1_1") (pintype "passive"))
      (node (ref "C5") (pin "2") (pinfunction "2_2") (pintype "passive"))
      (node (ref "C6") (pin "1") (pinfunction "1_1") (pintype "passive"))
      (node (ref "GND") (pin "1") (pinfunction "3_1") (pintype "passive"))
      (node (ref "GND1") (pin "1") (pinfunction "3_1") (pintype "passive"))
      (node (ref "GND2") (pin "1") (pinfunction "3_1") (pintype "passive"))
      (node (ref "GND3") (pin "1") (pinfunction "3_1") (pintype "passive"))
      (node (ref "GND4") (pin "1") (pinfunction "3_1") (pintype "passive"))
      (node (ref "GND5") (pin "1") (pinfunction "3_1") (pintype "passive"))
      (node (ref "IC1") (pin "10") (pinfunction "+IN_10") (pintype "input"))
      (node (ref "IC1") (pin "12") (pinfunction "+IN_12") (pintype "input"))
      (node (ref "IC1") (pin "3") (pinfunction "+IN_3") (pintype "input"))
      (node (ref "IC1") (pin "5") (pinfunction "+IN_5") (pintype "input"))
      (node (ref "IC3") (pin "10") (pinfunction "+IN_10") (pintype "input"))
      (node (ref "IC3") (pin "11") (pinfunction "V-_11") (pintype "power_in"))
      (node (ref "IC3") (pin "12") (pinfunction "+IN_12") (pintype "input"))
      (node (ref "IC3") (pin "3") (pinfunction "+IN_3") (pintype "input"))
      (node (ref "IC3") (pin "5") (pinfunction "+IN_5") (pintype "input"))
      (node (ref "IC4") (pin "10") (pinfunction "+IN_10") (pintype "input"))
      (node (ref "IC4") (pin "11") (pinfunction "V-_11") (pintype "power_in"))
      (node (ref "IC4") (pin "12") (pinfunction "+IN_12") (pintype "input"))
      (node (ref "IC4") (pin "3") (pinfunction "+IN_3") (pintype "input"))
      (node (ref "IC4") (pin "5") (pinfunction "+IN_5") (pintype "input"))
      (node (ref "IC7") (pin "2") (pinfunction "GND_2") (pintype "passive"))
      (node (ref "IC8") (pin "1") (pinfunction "C_1") (pintype "input"))
      (node (ref "IC9") (pin "10") (pinfunction "+IN_10") (pintype "input"))
      (node (ref "IC9") (pin "11") (pinfunction "V-_11") (pintype "power_in"))
      (node (ref "IC9") (pin "12") (pinfunction "+IN_12") (pintype "input"))
      (node (ref "IC9") (pin "3") (pinfunction "+IN_3") (pintype "input"))
      (node (ref "IC9") (pin "5") (pinfunction "+IN_5") (pintype "input"))
      (node (ref "U1") (pin "40") (pinfunction "GND_40") (pintype "bidirectional"))
    )
    (net (code "27") (name "Net-(0-3)") (class "Default")
      (node (ref "0") (pin "1") (pinfunction "3_1") (pintype "passive"))
      (node (ref "U1") (pin "1") (pinfunction "GPIO1(USB_HS_ID)_1") (pintype "bidirectional"))
    )
    (net (code "28") (name "Net-(1_SD_D3-3)") (class "Default")
      (node (ref "1_SD_D3") (pin "1") (pinfunction "3_1") (pintype "passive"))
      (node (ref "U1") (pin "2") (pinfunction "GPIO2(SDMMC1_D3)_2") (pintype "bidirectional"))
    )
    (net (code "29") (name "Net-(2_SD_D2-3)") (class "Default")
      (node (ref "2_SD_D2") (pin "1") (pinfunction "3_1") (pintype "passive"))
      (node (ref "U1") (pin "3") (pinfunction "GPIO3(SDMMC1_D2)_3") (pintype "bidirectional"))
    )
    (net (code "30") (name "Net-(3_SD_D1-3)") (class "Default")
      (node (ref "3_SD_D1") (pin "1") (pinfunction "3_1") (pintype "passive"))
      (node (ref "U1") (pin "4") (pinfunction "GPIO4(SDMMC1_D1)_4") (pintype "bidirectional"))
    )
    (net (code "31") (name "Net-(4_SD_D0-3)") (class "Default")
      (node (ref "4_SD_D0") (pin "1") (pinfunction "3_1") (pintype "passive"))
      (node (ref "U1") (pin "5") (pinfunction "GPIO5(SDMMC1_D0)_5") (pintype "bidirectional"))
    )
    (net (code "32") (name "Net-(5_SD_CMD-3)") (class "Default")
      (node (ref "5_SD_CMD") (pin "1") (pinfunction "3_1") (pintype "passive"))
      (node (ref "U1") (pin "6") (pinfunction "GPIO6(SDMMC1_CMD)_6") (pintype "bidirectional"))
    )
    (net (code "33") (name "Net-(6_SD_CK-3)") (class "Default")
      (node (ref "6_SD_CK") (pin "1") (pinfunction "3_1") (pintype "passive"))
      (node (ref "U1") (pin "7") (pinfunction "GPIO7(SDMMC1_CK)_7") (pintype "bidirectional"))
    )
    (net (code "34") (name "Net-(7_CS-3)") (class "Default")
      (node (ref "7_CS") (pin "1") (pinfunction "3_1") (pintype "passive"))
      (node (ref "U1") (pin "8") (pinfunction "GPIO8(SPI1_NSS)_8") (pintype "bidirectional"))
    )
    (net (code "35") (name "Net-(11_SCL-3)") (class "Default")
      (node (ref "11_SCL") (pin "1") (pinfunction "3_1") (pintype "passive"))
      (node (ref "U1") (pin "12") (pinfunction "GPIO12(I2C1_SCL)_12") (pintype "bidirectional"))
    )
    (net (code "36") (name "Net-(12_SDA-3)") (class "Default")
      (node (ref "12_SDA") (pin "1") (pinfunction "3_1") (pintype "passive"))
      (node (ref "U1") (pin "13") (pinfunction "GPIO13(I2C1_SDA)_13") (pintype "bidirectional"))
    )
    (net (code "37") (name "Net-(13_TX-3)") (class "Default")
      (node (ref "13_TX") (pin "1") (pinfunction "3_1") (pintype "passive"))
      (node (ref "U1") (pin "14") (pinfunction "GPIO14(USART1_TX)_14") (pintype "bidirectional"))
    )
    (net (code "38") (name "Net-(14_RX-3)") (class "Default")
      (node (ref "14_RX") (pin "1") (pinfunction "3_1") (pintype "passive"))
      (node (ref "U1") (pin "15") (pinfunction "GPIO15(USART1_RX)_15") (pintype "bidirectional"))
    )
    (net (code "39") (name "Net-(27-3)") (class "Default")
      (node (ref "27") (pin "1") (pinfunction "3_1") (pintype "passive"))
      (node (ref "U1") (pin "34") (pinfunction "GPIO28(SAI2_FS_B)_34") (pintype "bidirectional"))
    )
    (net (code "40") (name "Net-(29-3)") (class "Default")
      (node (ref "29") (pin "1") (pinfunction "3_1") (pintype "passive"))
      (node (ref "U1") (pin "36") (pinfunction "GPIO30(USB_HS_D_-)_36") (pintype "bidirectional"))
    )
    (net (code "41") (name "Net-(30-3)") (class "Default")
      (node (ref "30") (pin "1") (pinfunction "3_1") (pintype "passive"))
      (node (ref "U1") (pin "37") (pinfunction "GPIO31(USB_HS_D+)_37") (pintype "bidirectional"))
    )
    (net (code "42") (name "Net-(AIN_L-3)") (class "Default")
      (node (ref "AIN_L") (pin "1") (pinfunction "3_1") (pintype "passive"))
      (node (ref "R17") (pin "2") (pinfunction "2_2") (pintype "passive"))
    )
    (net (code "43") (name "Net-(AIN_R-3)") (class "Default")
      (node (ref "AIN_R") (pin "1") (pinfunction "3_1") (pintype "passive"))
      (node (ref "R14") (pin "2") (pinfunction "2_2") (pintype "passive"))
    )
    (net (code "44") (name "Net-(AOUT_L-3)") (class "Default")
      (node (ref "AOUT_L") (pin "1") (pinfunction "3_1") (pintype "passive"))
      (node (ref "R3") (pin "2") (pinfunction "2_2") (pintype "passive"))
    )
    (net (code "45") (name "Net-(AOUT_R-3)") (class "Default")
      (node (ref "AOUT_R") (pin "1") (pinfunction "3_1") (pintype "passive"))
      (node (ref "R6") (pin "2") (pinfunction "2_2") (pintype "passive"))
    )
    (net (code "46") (name "Net-(CV1-3)") (class "Default")
      (node (ref "CV1") (pin "1") (pinfunction "3_1") (pintype "passive"))
      (node (ref "R31") (pin "1") (pinfunction "1_1") (pintype "passive"))
    )
    (net (code "47") (name "Net-(CV1B-3)") (class "Default")
      (node (ref "CV1B") (pin "1") (pinfunction "3_1") (pintype "passive"))
      (node (ref "R23") (pin "1") (pinfunction "1_1") (pintype "passive"))
    )
    (net (code "48") (name "Net-(CV2-3)") (class "Default")
      (node (ref "CV2") (pin "1") (pinfunction "3_1") (pintype "passive"))
      (node (ref "R27") (pin "1") (pinfunction "1_1") (pintype "passive"))
    )
    (net (code "49") (name "Net-(CV2B-3)") (class "Default")
      (node (ref "CV2B") (pin "1") (pinfunction "3_1") (pintype "passive"))
      (node (ref "R28") (pin "1") (pinfunction "1_1") (pintype "passive"))
    )
    (net (code "50") (name "Net-(CV3-3)") (class "Default")
      (node (ref "CV3") (pin "1") (pinfunction "3_1") (pintype "passive"))
      (node (ref "R22") (pin "1") (pinfunction "1_1") (pintype "passive"))
    )
    (net (code "51") (name "Net-(CV3B-3)") (class "Default")
      (node (ref "CV3B") (pin "1") (pinfunction "3_1") (pintype "passive"))
      (node (ref "R32") (pin "1") (pinfunction "1_1") (pintype "passive"))
    )
    (net (code "52") (name "Net-(CV4-3)") (class "Default")
      (node (ref "CV4") (pin "1") (pinfunction "3_1") (pintype "passive"))
      (node (ref "R35") (pin "1") (pinfunction "1_1") (pintype "passive"))
    )
    (net (code "53") (name "Net-(CV4B-3)") (class "Default")
      (node (ref "CV4B") (pin "1") (pinfunction "3_1") (pintype "passive"))
      (node (ref "R36") (pin "1") (pinfunction "1_1") (pintype "passive"))
    )
    (net (code "54") (name "Net-(CV5-3)") (class "Default")
      (node (ref "CV5") (pin "1") (pinfunction "3_1") (pintype "passive"))
      (node (ref "R65") (pin "1") (pinfunction "1_1") (pintype "passive"))
    )
    (net (code "55") (name "Net-(CV6-3)") (class "Default")
      (node (ref "CV6") (pin "1") (pinfunction "3_1") (pintype "passive"))
      (node (ref "R62") (pin "1") (pinfunction "1_1") (pintype "passive"))
    )
    (net (code "56") (name "Net-(CV7-3)") (class "Default")
      (node (ref "CV7") (pin "1") (pinfunction "3_1") (pintype "passive"))
      (node (ref "R11") (pin "1") (pinfunction "1_1") (pintype "passive"))
    )
    (net (code "57") (name "Net-(CV8-3)") (class "Default")
      (node (ref "CV8") (pin "1") (pinfunction "3_1") (pintype "passive"))
      (node (ref "R69") (pin "1") (pinfunction "1_1") (pintype "passive"))
    )
    (net (code "58") (name "Net-(CV9-3)") (class "Default")
      (node (ref "CV9") (pin "1") (pinfunction "3_1") (pintype "passive"))
      (node (ref "R92") (pin "1") (pinfunction "1_1") (pintype "passive"))
    )
    (net (code "59") (name "Net-(CV9B-3)") (class "Default")
      (node (ref "CV9B") (pin "1") (pinfunction "3_1") (pintype "passive"))
      (node (ref "R12") (pin "1") (pinfunction "1_1") (pintype "passive"))
    )
    (net (code "60") (name "Net-(CV10-3)") (class "Default")
      (node (ref "CV10") (pin "1") (pinfunction "3_1") (pintype "passive"))
      (node (ref "R89") (pin "1") (pinfunction "1_1") (pintype "passive"))
    )
    (net (code "61") (name "Net-(CV10B-3)") (class "Default")
      (node (ref "CV10B") (pin "1") (pinfunction "3_1") (pintype "passive"))
      (node (ref "R63") (pin "1") (pinfunction "1_1") (pintype "passive"))
    )
    (net (code "62") (name "Net-(CV11-3)") (class "Default")
      (node (ref "CV11") (pin "1") (pinfunction "3_1") (pintype "passive"))
      (node (ref "R84") (pin "1") (pinfunction "1_1") (pintype "passive"))
    )
    (net (code "63") (name "Net-(CV11B-3)") (class "Default")
      (node (ref "CV11B") (pin "1") (pinfunction "3_1") (pintype "passive"))
      (node (ref "R66") (pin "1") (pinfunction "1_1") (pintype "passive"))
    )
    (net (code "64") (name "Net-(CV12-3)") (class "Default")
      (node (ref "CV12") (pin "1") (pinfunction "3_1") (pintype "passive"))
      (node (ref "R96") (pin "1") (pinfunction "1_1") (pintype "passive"))
    )
    (net (code "65") (name "Net-(CV12B-3)") (class "Default")
      (node (ref "CV12B") (pin "1") (pinfunction "3_1") (pintype "passive"))
      (node (ref "R70") (pin "1") (pinfunction "1_1") (pintype "passive"))
    )
    (net (code "66") (name "Net-(CV13B-3)") (class "Default")
      (node (ref "CV13B") (pin "1") (pinfunction "3_1") (pintype "passive"))
      (node (ref "R85") (pin "1") (pinfunction "1_1") (pintype "passive"))
    )
    (net (code "67") (name "Net-(CV14B-3)") (class "Default")
      (node (ref "CV14B") (pin "1") (pinfunction "3_1") (pintype "passive"))
      (node (ref "R90") (pin "1") (pinfunction "1_1") (pintype "passive"))
    )
    (net (code "68") (name "Net-(CV15B-3)") (class "Default")
      (node (ref "CV15B") (pin "1") (pinfunction "3_1") (pintype "passive"))
      (node (ref "R93") (pin "1") (pinfunction "1_1") (pintype "passive"))
    )
    (net (code "69") (name "Net-(CV16B-3)") (class "Default")
      (node (ref "CV16B") (pin "1") (pinfunction "3_1") (pintype "passive"))
      (node (ref "R97") (pin "1") (pinfunction "1_1") (pintype "passive"))
    )
    (net (code "70") (name "Net-(IC1A--IN)") (class "Default")
      (node (ref "C8") (pin "1") (pinfunction "1_1") (pintype "passive"))
      (node (ref "IC1") (pin "2") (pinfunction "-IN_2") (pintype "input"))
      (node (ref "R1") (pin "2") (pinfunction "2_2") (pintype "passive"))
      (node (ref "R2") (pin "1") (pinfunction "1_1") (pintype "passive"))
    )
    (net (code "71") (name "Net-(IC1A-OUT)") (class "Default")
      (node (ref "C8") (pin "2") (pinfunction "2_2") (pintype "passive"))
      (node (ref "IC1") (pin "1") (pinfunction "OUT_1") (pintype "output"))
      (node (ref "R2") (pin "2") (pinfunction "2_2") (pintype "passive"))
      (node (ref "R3") (pin "1") (pinfunction "1_1") (pintype "passive"))
    )
    (net (code "72") (name "Net-(IC1B--IN)") (class "Default")
      (node (ref "C9") (pin "1") (pinfunction "1_1") (pintype "passive"))
      (node (ref "IC1") (pin "6") (pinfunction "-IN_6") (pintype "input"))
      (node (ref "R4") (pin "2") (pinfunction "2_2") (pintype "passive"))
      (node (ref "R5") (pin "1") (pinfunction "1_1") (pintype "passive"))
    )
    (net (code "73") (name "Net-(IC1B-OUT)") (class "Default")
      (node (ref "C9") (pin "2") (pinfunction "2_2") (pintype "passive"))
      (node (ref "IC1") (pin "7") (pinfunction "OUT_7") (pintype "output"))
      (node (ref "R5") (pin "2") (pinfunction "2_2") (pintype "passive"))
      (node (ref "R6") (pin "1") (pinfunction "1_1") (pintype "passive"))
    )
    (net (code "74") (name "Net-(IC1C--IN)") (class "Default")
      (node (ref "C12") (pin "1") (pinfunction "1_1") (pintype "passive"))
      (node (ref "IC1") (pin "9") (pinfunction "-IN_9") (pintype "input"))
      (node (ref "R10") (pin "2") (pinfunction "2_2") (pintype "passive"))
      (node (ref "R9") (pin "1") (pinfunction "1_1") (pintype "passive"))
    )
    (net (code "75") (name "Net-(IC1C-OUT)") (class "Default")
      (node (ref "C12") (pin "2") (pinfunction "2_2") (pintype "passive"))
      (node (ref "IC1") (pin "8") (pinfunction "OUT_8") (pintype "output"))
      (node (ref "R14") (pin "1") (pinfunction "1_1") (pintype "passive"))
      (node (ref "R9") (pin "2") (pinfunction "2_2") (pintype "passive"))
    )
    (net (code "76") (name "Net-(IC1D--IN)") (class "Default")
      (node (ref "C13") (pin "1") (pinfunction "1_1") (pintype "passive"))
      (node (ref "IC1") (pin "13") (pinfunction "-IN_13") (pintype "input"))
      (node (ref "R16") (pin "1") (pinfunction "1_1") (pintype "passive"))
      (node (ref "R18") (pin "2") (pinfunction "2_2") (pintype "passive"))
    )
    (net (code "77") (name "Net-(IC1D-OUT)") (class "Default")
      (node (ref "C13") (pin "2") (pinfunction "2_2") (pintype "passive"))
      (node (ref "IC1") (pin "14") (pinfunction "OUT_14") (pintype "output"))
      (node (ref "R16") (pin "2") (pinfunction "2_2") (pintype "passive"))
      (node (ref "R17") (pin "1") (pinfunction "1_1") (pintype "passive"))
    )
    (net (code "78") (name "Net-(IC3A--IN)") (class "Default")
      (node (ref "C7") (pin "1") (pinfunction "1_1") (pintype "passive"))
      (node (ref "IC3") (pin "2") (pinfunction "-IN_2") (pintype "input"))
      (node (ref "R11") (pin "2") (pinfunction "2_2") (pintype "passive"))
      (node (ref "R12") (pin "2") (pinfunction "2_2") (pintype "passive"))
      (node (ref "R13") (pin "2") (pinfunction "2_2") (pintype "passive"))
      (node (ref "R8") (pin "1") (pinfunction "1_1") (pintype "passive"))
    )
    (net (code "79") (name "Net-(IC3B--IN)") (class "Default")
      (node (ref "C10") (pin "1") (pinfunction "1_1") (pintype "passive"))
      (node (ref "IC3") (pin "6") (pinfunction "-IN_6") (pintype "input"))
      (node (ref "R15") (pin "1") (pinfunction "1_1") (pintype "passive"))
      (node (ref "R29") (pin "2") (pinfunction "2_2") (pintype "passive"))
      (node (ref "R62") (pin "2") (pinfunction "2_2") (pintype "passive"))
      (node (ref "R63") (pin "2") (pinfunction "2_2") (pintype "passive"))
    )
    (net (code "80") (name "Net-(IC3C--IN)") (class "Default")
      (node (ref "C11") (pin "1") (pinfunction "1_1") (pintype "passive"))
      (node (ref "IC3") (pin "9") (pinfunction "-IN_9") (pintype "input"))
      (node (ref "R64") (pin "1") (pinfunction "1_1") (pintype "passive"))
      (node (ref "R65") (pin "2") (pinfunction "2_2") (pintype "passive"))
      (node (ref "R66") (pin "2") (pinfunction "2_2") (pintype "passive"))
      (node (ref "R67") (pin "2") (pinfunction "2_2") (pintype "passive"))
    )
    (net (code "81") (name "Net-(IC3D--IN)") (class "Default")
      (node (ref "C14") (pin "1") (pinfunction "1_1") (pintype "passive"))
      (node (ref "IC3") (pin "13") (pinfunction "-IN_13") (pintype "input"))
      (node (ref "R68") (pin "1") (pinfunction "1_1") (pintype "passive"))
      (node (ref "R69") (pin "2") (pinfunction "2_2") (pintype "passive"))
      (node (ref "R70") (pin "2") (pinfunction "2_2") (pintype "passive"))
      (node (ref "R71") (pin "2") (pinfunction "2_2") (pintype "passive"))
    )
    (net (code "82") (name "Net-(IC4A--IN)") (class "Default")
      (node (ref "C16") (pin "1") (pinfunction "1_1") (pintype "passive"))
      (node (ref "IC4") (pin "2") (pinfunction "-IN_2") (pintype "input"))
      (node (ref "R21") (pin "1") (pinfunction "1_1") (pintype "passive"))
      (node (ref "R22") (pin "2") (pinfunction "2_2") (pintype "passive"))
      (node (ref "R23") (pin "2") (pinfunction "2_2") (pintype "passive"))
      (node (ref "R24") (pin "2") (pinfunction "2_2") (pintype "passive"))
    )
    (net (code "83") (name "Net-(IC4B--IN)") (class "Default")
      (node (ref "C17") (pin "1") (pinfunction "1_1") (pintype "passive"))
      (node (ref "IC4") (pin "6") (pinfunction "-IN_6") (pintype "input"))
      (node (ref "R25") (pin "1") (pinfunction "1_1") (pintype "passive"))
      (node (ref "R26") (pin "2") (pinfunction "2_2") (pintype "passive"))
      (node (ref "R27") (pin "2") (pinfunction "2_2") (pintype "passive"))
      (node (ref "R28") (pin "2") (pinfunction "2_2") (pintype "passive"))
    )
    (net (code "84") (name "Net-(IC4C--IN)") (class "Default")
      (node (ref "C20") (pin "1") (pinfunction "1_1") (pintype "passive"))
      (node (ref "IC4") (pin "9") (pinfunction "-IN_9") (pintype "input"))
      (node (ref "R30") (pin "1") (pinfunction "1_1") (pintype "passive"))
      (node (ref "R31") (pin "2") (pinfunction "2_2") (pintype "passive"))
      (node (ref "R32") (pin "2") (pinfunction "2_2") (pintype "passive"))
      (node (ref "R33") (pin "2") (pinfunction "2_2") (pintype "passive"))
    )
    (net (code "85") (name "Net-(IC4D--IN)") (class "Default")
      (node (ref "C21") (pin "1") (pinfunction "1_1") (pintype "passive"))
      (node (ref "IC4") (pin "13") (pinfunction "-IN_13") (pintype "input"))
      (node (ref "R34") (pin "1") (pinfunction "1_1") (pintype "passive"))
      (node (ref "R35") (pin "2") (pinfunction "2_2") (pintype "passive"))
      (node (ref "R36") (pin "2") (pinfunction "2_2") (pintype "passive"))
      (node (ref "R37") (pin "2") (pinfunction "2_2") (pintype "passive"))
    )
    (net (code "86") (name "Net-(IC7-VI)") (class "Default")
      (node (ref "IC7") (pin "1") (pinfunction "VI_1") (pintype "input"))
      (node (ref "L1") (pin "2") (pinfunction "2_2") (pintype "passive"))
    )
    (net (code "87") (name "Net-(IC9A--IN)") (class "Default")
      (node (ref "C28") (pin "1") (pinfunction "1_1") (pintype "passive"))
      (node (ref "IC9") (pin "2") (pinfunction "-IN_2") (pintype "input"))
      (node (ref "R83") (pin "1") (pinfunction "1_1") (pintype "passive"))
      (node (ref "R84") (pin "2") (pinfunction "2_2") (pintype "passive"))
      (node (ref "R85") (pin "2") (pinfunction "2_2") (pintype "passive"))
      (node (ref "R86") (pin "2") (pinfunction "2_2") (pintype "passive"))
    )
    (net (code "88") (name "Net-(IC9B--IN)") (class "Default")
      (node (ref "C29") (pin "1") (pinfunction "1_1") (pintype "passive"))
      (node (ref "IC9") (pin "6") (pinfunction "-IN_6") (pintype "input"))
      (node (ref "R87") (pin "1") (pinfunction "1_1") (pintype "passive"))
      (node (ref "R88") (pin "2") (pinfunction "2_2") (pintype "passive"))
      (node (ref "R89") (pin "2") (pinfunction "2_2") (pintype "passive"))
      (node (ref "R90") (pin "2") (pinfunction "2_2") (pintype "passive"))
    )
    (net (code "89") (name "Net-(IC9C--IN)") (class "Default")
      (node (ref "C30") (pin "1") (pinfunction "1_1") (pintype "passive"))
      (node (ref "IC9") (pin "9") (pinfunction "-IN_9") (pintype "input"))
      (node (ref "R91") (pin "1") (pinfunction "1_1") (pintype "passive"))
      (node (ref "R92") (pin "2") (pinfunction "2_2") (pintype "passive"))
      (node (ref "R93") (pin "2") (pinfunction "2_2") (pintype "passive"))
      (node (ref "R94") (pin "2") (pinfunction "2_2") (pintype "passive"))
    )
    (net (code "90") (name "Net-(IC9D--IN)") (class "Default")
      (node (ref "C31") (pin "1") (pinfunction "1_1") (pintype "passive"))
      (node (ref "IC9") (pin "13") (pinfunction "-IN_13") (pintype "input"))
      (node (ref "R95") (pin "1") (pinfunction "1_1") (pintype "passive"))
      (node (ref "R96") (pin "2") (pinfunction "2_2") (pintype "passive"))
      (node (ref "R97") (pin "2") (pinfunction "2_2") (pintype "passive"))
      (node (ref "R98") (pin "2") (pinfunction "2_2") (pintype "passive"))
    )
    (net (code "91") (name "unconnected-(U1-+3V3_A-Pad21)") (class "Default")
      (node (ref "U1") (pin "21") (pinfunction "+3V3_A_21") (pintype "bidirectional"))
    )
    (net (code "92") (name "unconnected-(U1-AGND-Pad20)") (class "Default")
      (node (ref "U1") (pin "20") (pinfunction "AGND_20") (pintype "bidirectional"))
    )
  )
)
